# EPS_Battery_Controller_Voltage-Meas.net
KiCad netlist of a schematic drawn in Altium Designer
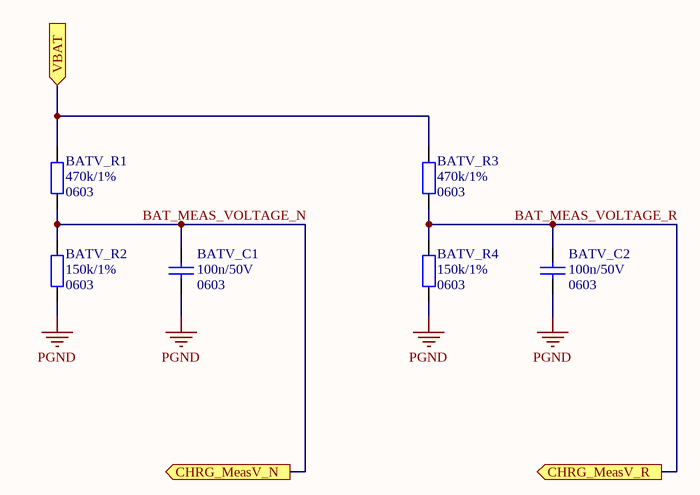
[diagram p0: EPS_Battery_Controller_Voltage-Meas.SchDoc]

(export (version "E")
  (design (tool "Eeschema 10.0.6"))
  (components
    (comp (ref "BATV_C1")
      (value "100n/50V")
      (footprint "SMD_Capacitor_0603")
      (description "Ceramic Cap Kemet COTS 100n/50V X7R 0603")
      (fields
        (field (name "MANUFACTURER") "Kemet")
        (field (name "MANUFACTURERPARTNUMBER") "C0603T104K5RALTU")
        (field (name "PACKAGE") "0603")
      )
      (libsource (lib "capacitors") (part "Cer_C0603T104K5RALTU"))
    )
    (comp (ref "BATV_C2")
      (value "100n/50V")
      (footprint "SMD_Capacitor_0603")
      (description "Ceramic Cap Kemet COTS 100n/50V X7R 0603")
      (fields
        (field (name "MANUFACTURER") "Kemet")
        (field (name "MANUFACTURERPARTNUMBER") "C0603T104K5RALTU")
        (field (name "PACKAGE") "0603")
      )
      (libsource (lib "capacitors") (part "Cer_C0603T104K5RALTU"))
    )
    (comp (ref "BATV_R1")
      (value "470k/1%")
      (footprint "SMD_Resistor_0603")
      (fields (field (name "PACKAGE") "0603"))
      (libsource (lib "resistors") (part "Res"))
    )
    (comp (ref "BATV_R2")
      (value "150k/1%")
      (footprint "SMD_Resistor_0603")
      (fields (field (name "PACKAGE") "0603"))
      (libsource (lib "resistors") (part "Res"))
    )
    (comp (ref "BATV_R3")
      (value "470k/1%")
      (footprint "SMD_Resistor_0603")
      (fields (field (name "PACKAGE") "0603"))
      (libsource (lib "resistors") (part "Res"))
    )
    (comp (ref "BATV_R4")
      (value "150k/1%")
      (footprint "SMD_Resistor_0603")
      (fields (field (name "PACKAGE") "0603"))
      (libsource (lib "resistors") (part "Res"))
    )
  )
  (nets
    (net (code "1") (name "/BAT_MEAS_VOLTAGE_N") (class "Default")
      (node (ref "BATV_C1") (pin "1") (pinfunction "1_1") (pintype "passive"))
      (node (ref "BATV_R1") (pin "2") (pinfunction "2_2") (pintype "passive"))
      (node (ref "BATV_R2") (pin "1") (pinfunction "1_1") (pintype "passive"))
    )
    (net (code "2") (name "/BAT_MEAS_VOLTAGE_R") (class "Default")
      (node (ref "BATV_C2") (pin "1") (pinfunction "1_1") (pintype "passive"))
      (node (ref "BATV_R3") (pin "2") (pinfunction "2_2") (pintype "passive"))
      (node (ref "BATV_R4") (pin "1") (pinfunction "1_1") (pintype "passive"))
    )
    (net (code "3") (name "/VBAT") (class "Default")
      (node (ref "BATV_R1") (pin "1") (pinfunction "1_1") (pintype "passive"))
      (node (ref "BATV_R3") (pin "1") (pinfunction "1_1") (pintype "passive"))
    )
    (net (code "4") (name "PGND") (class "Default")
      (node (ref "BATV_C1") (pin "2") (pinfunction "2_2") (pintype "passive"))
      (node (ref "BATV_C2") (pin "2") (pinfunction "2_2") (pintype "passive"))
      (node (ref "BATV_R2") (pin "2") (pinfunction "2_2") (pintype "passive"))
      (node (ref "BATV_R4") (pin "2") (pinfunction "2_2") (pintype "passive"))
    )
  )
)
